# AD8361.net
KiCad netlist of a schematic drawn in Altium Designer
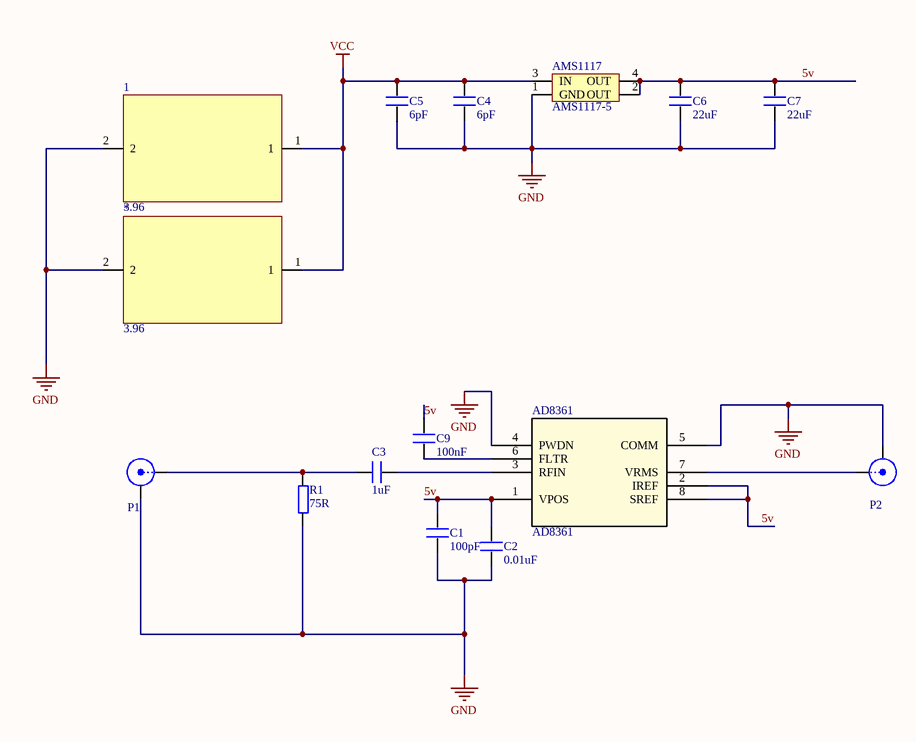
[diagram p0: AD8361.SchDoc]

(export (version "E")
  (design (tool "Eeschema 10.0.6"))
  (components
    (comp (ref "*") (value "3.96") (footprint "3.96") (libsource (lib "MYLIB") (part "3.96")))
    (comp (ref "1") (value "3.96") (footprint "3.96") (libsource (lib "MYLIB") (part "3.96")))
    (comp (ref "AD8361")
      (value "AD8361")
      (footprint "RM_8")
      (description "LF至2.5 GHz TruPwr™检波器")
      (fields
        (field (name "MANUFACTURER_PART_NUMBER") "AD8361ARMZ")
        (field (name "COPYRIGHT") "Copyright (C) 2018 Accelerated Designs. All rights reserved")
      )
      (libsource (lib "MYLIB") (part "AD8361"))
    )
    (comp (ref "AMS1117")
      (value "AMS1117-5")
      (footprint "AMS1117")
      (libsource (lib "MYLIB") (part "AMS1117"))
    )
    (comp (ref "C1")
      (value "100pF")
      (footprint "0603C")
      (description "Capacitor")
      (libsource (lib "MYLIB") (part "C"))
    )
    (comp (ref "C2")
      (value "0.01uF")
      (footprint "0603C")
      (description "Capacitor")
      (libsource (lib "MYLIB") (part "C"))
    )
    (comp (ref "C3")
      (value "1uF")
      (footprint "0603C")
      (description "Capacitor")
      (libsource (lib "MYLIB") (part "C"))
    )
    (comp (ref "C4")
      (value "6pF")
      (footprint "0603C")
      (description "Capacitor")
      (libsource (lib "MYLIB") (part "C"))
    )
    (comp (ref "C5")
      (value "6pF")
      (footprint "1206C")
      (description "Capacitor")
      (libsource (lib "MYLIB") (part "C"))
    )
    (comp (ref "C6")
      (value "22uF")
      (footprint "1206C")
      (description "Capacitor")
      (libsource (lib "MYLIB") (part "C"))
    )
    (comp (ref "C7")
      (value "22uF")
      (footprint "0603C")
      (description "Capacitor")
      (libsource (lib "MYLIB") (part "C"))
    )
    (comp (ref "C9")
      (value "100nF")
      (footprint "0603C")
      (description "Capacitor")
      (libsource (lib "MYLIB") (part "C"))
    )
    (comp (ref "P1")
      (value "SMA")
      (footprint "SMA")
      (description "SMA Connector")
      (libsource (lib "MYLIB") (part "SMA"))
    )
    (comp (ref "P2")
      (value "SMA")
      (footprint "SMA")
      (description "SMA Connector")
      (libsource (lib "MYLIB") (part "SMA"))
    )
    (comp (ref "R1")
      (value "75R")
      (footprint "0603R")
      (description "Resistor")
      (libsource (lib "MYLIB") (part "Resistor"))
    )
  )
  (nets
    (net (code "1") (name "/5v") (class "Default")
      (node (ref "AD8361") (pin "1") (pinfunction "VPOS_1") (pintype "power_in"))
      (node (ref "AD8361") (pin "2") (pinfunction "IREF_2") (pintype "power_in"))
      (node (ref "AD8361") (pin "8") (pinfunction "SREF_8") (pintype "passive"))
      (node (ref "AMS1117") (pin "2") (pinfunction "OUT_2") (pintype "passive"))
      (node (ref "AMS1117") (pin "4") (pinfunction "OUT_4") (pintype "passive"))
      (node (ref "C1") (pin "2") (pintype "passive"))
      (node (ref "C2") (pin "2") (pintype "passive"))
      (node (ref "C6") (pin "2") (pintype "passive"))
      (node (ref "C7") (pin "2") (pintype "passive"))
      (node (ref "C9") (pin "2") (pintype "passive"))
    )
    (net (code "2") (name "GND") (class "Default")
      (node (ref "*") (pin "2") (pinfunction "2_2") (pintype "passive"))
      (node (ref "1") (pin "2") (pinfunction "2_2") (pintype "passive"))
      (node (ref "AD8361") (pin "4") (pinfunction "PWDN_4") (pintype "passive"))
      (node (ref "AD8361") (pin "5") (pinfunction "COMM_5") (pintype "passive"))
      (node (ref "AMS1117") (pin "1") (pinfunction "GND_1") (pintype "passive"))
      (node (ref "C1") (pin "1") (pintype "passive"))
      (node (ref "C2") (pin "1") (pintype "passive"))
      (node (ref "C4") (pin "1") (pintype "passive"))
      (node (ref "C5") (pin "1") (pintype "passive"))
      (node (ref "C6") (pin "1") (pintype "passive"))
      (node (ref "C7") (pin "1") (pintype "passive"))
      (node (ref "P1") (pin "2") (pinfunction "Y_2") (pintype "passive"))
      (node (ref "P2") (pin "2") (pinfunction "Y_2") (pintype "passive"))
      (node (ref "R1") (pin "1") (pintype "passive"))
    )
    (net (code "3") (name "Net-(AD8361-FLTR)") (class "Default")
      (node (ref "AD8361") (pin "6") (pinfunction "FLTR_6") (pintype "passive"))
      (node (ref "C9") (pin "1") (pintype "passive"))
    )
    (net (code "4") (name "Net-(AD8361-RFIN)") (class "Default")
      (node (ref "AD8361") (pin "3") (pinfunction "RFIN_3") (pintype "passive"))
      (node (ref "C3") (pin "1") (pintype "passive"))
    )
    (net (code "5") (name "Net-(AD8361-VRMS)") (class "Default")
      (node (ref "AD8361") (pin "7") (pinfunction "VRMS_7") (pintype "passive"))
      (node (ref "P2") (pin "1") (pinfunction "X_1") (pintype "passive"))
    )
    (net (code "6") (name "Net-(P1-X)") (class "Default")
      (node (ref "C3") (pin "2") (pintype "passive"))
      (node (ref "P1") (pin "1") (pinfunction "X_1") (pintype "passive"))
      (node (ref "R1") (pin "2") (pintype "passive"))
    )
    (net (code "7") (name "VCC") (class "Default")
      (node (ref "*") (pin "1") (pinfunction "1_1") (pintype "passive"))
      (node (ref "1") (pin "1") (pinfunction "1_1") (pintype "passive"))
      (node (ref "AMS1117") (pin "3") (pinfunction "IN_3") (pintype "passive"))
      (node (ref "C4") (pin "2") (pintype "passive"))
      (node (ref "C5") (pin "2") (pintype "passive"))
    )
  )
)
